# Part_2_PS_Controller.net
KiCad netlist of a schematic drawn in Altium Designer
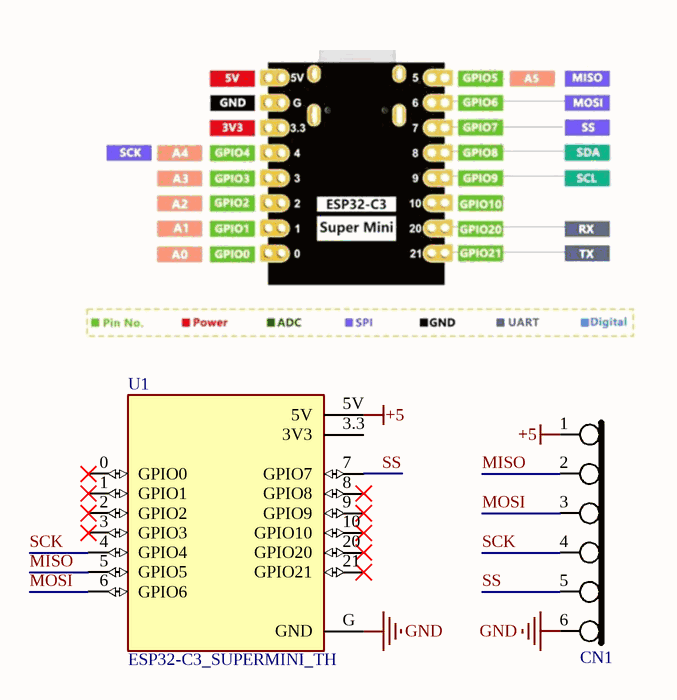
[diagram p0: Part_2_PS_Controller.SchDoc]

(export (version "E")
  (design (tool "Eeschema 10.0.6"))
  (components
    (comp (ref "CN1")
      (value "CN_6P_Header 1 Row")
      (footprint "HD6-2.54")
      (description "Jump Header 6P 1Row")
      (libsource (lib "TIFATECH") (part "CN_6P_Header 1 Row"))
    )
    (comp (ref "U1")
      (value "ESP32-C3_SUPERMINI_TH")
      (footprint "MODULE_ESP32-C3_SUPERMINI_TH")
      (description "Super tiny ESP32-C3 board")
      (fields (field (name "MF") "Espressif Systems") (field (name "MP") "ESP32-C3 SuperMini_TH"))
      (libsource (lib "ESP32-C3_SUPERMINI_TH") (part "ESP32-C3_SUPERMINI_TH"))
    )
  )
  (nets
    (net (code "1") (name "+5") (class "Default")
      (node (ref "CN1") (pin "1") (pinfunction "1_1") (pintype "passive"))
      (node (ref "U1") (pin "5V") (pinfunction "5V_5V") (pintype "power_in"))
    )
    (net (code "2") (name "/MISO") (class "Default")
      (node (ref "CN1") (pin "2") (pinfunction "2_2") (pintype "passive"))
      (node (ref "U1") (pin "5") (pinfunction "GPIO5_5") (pintype "bidirectional"))
    )
    (net (code "3") (name "/MOSI") (class "Default")
      (node (ref "CN1") (pin "3") (pinfunction "4_3") (pintype "passive"))
      (node (ref "U1") (pin "6") (pinfunction "GPIO6_6") (pintype "bidirectional"))
    )
    (net (code "4") (name "/SCK") (class "Default")
      (node (ref "CN1") (pin "4") (pinfunction "6_4") (pintype "passive"))
      (node (ref "U1") (pin "4") (pinfunction "GPIO4_4") (pintype "bidirectional"))
    )
    (net (code "5") (name "/SS") (class "Default")
      (node (ref "CN1") (pin "5") (pinfunction "8_5") (pintype "passive"))
      (node (ref "U1") (pin "7") (pinfunction "GPIO7_7") (pintype "bidirectional"))
    )
    (net (code "6") (name "GND") (class "Default")
      (node (ref "CN1") (pin "6") (pinfunction "10_6") (pintype "passive"))
      (node (ref "U1") (pin "G") (pinfunction "GND_G") (pintype "power_in"))
    )
    (net (code "7") (name "unconnected-(U1-3V3-Pad3.3)") (class "Default")
      (node (ref "U1") (pin "3.3") (pinfunction "3V3_3.3") (pintype "power_in"))
    )
    (net (code "8") (name "unconnected-(U1-GPIO0-Pad0)") (class "Default")
      (node (ref "U1") (pin "0") (pinfunction "GPIO0_0") (pintype "bidirectional+no_connect"))
    )
    (net (code "9") (name "unconnected-(U1-GPIO1-Pad1)") (class "Default")
      (node (ref "U1") (pin "1") (pinfunction "GPIO1_1") (pintype "bidirectional+no_connect"))
    )
    (net (code "10") (name "unconnected-(U1-GPIO2-Pad2)") (class "Default")
      (node (ref "U1") (pin "2") (pinfunction "GPIO2_2") (pintype "bidirectional+no_connect"))
    )
    (net (code "11") (name "unconnected-(U1-GPIO3-Pad3)") (class "Default")
      (node (ref "U1") (pin "3") (pinfunction "GPIO3_3") (pintype "bidirectional+no_connect"))
    )
    (net (code "12") (name "unconnected-(U1-GPIO8-Pad8)") (class "Default")
      (node (ref "U1") (pin "8") (pinfunction "GPIO8_8") (pintype "bidirectional+no_connect"))
    )
    (net (code "13") (name "unconnected-(U1-GPIO9-Pad9)") (class "Default")
      (node (ref "U1") (pin "9") (pinfunction "GPIO9_9") (pintype "bidirectional+no_connect"))
    )
    (net (code "14") (name "unconnected-(U1-GPIO10-Pad10)") (class "Default")
      (node (ref "U1") (pin "10") (pinfunction "GPIO10_10") (pintype "bidirectional+no_connect"))
    )
    (net (code "15") (name "unconnected-(U1-GPIO20-Pad20)") (class "Default")
      (node (ref "U1") (pin "20") (pinfunction "GPIO20_20") (pintype "bidirectional+no_connect"))
    )
    (net (code "16") (name "unconnected-(U1-GPIO21-Pad21)") (class "Default")
      (node (ref "U1") (pin "21") (pinfunction "GPIO21_21") (pintype "bidirectional+no_connect"))
    )
  )
)
